# PP5_MIDI.net
KiCad netlist of a schematic drawn in Altium Designer
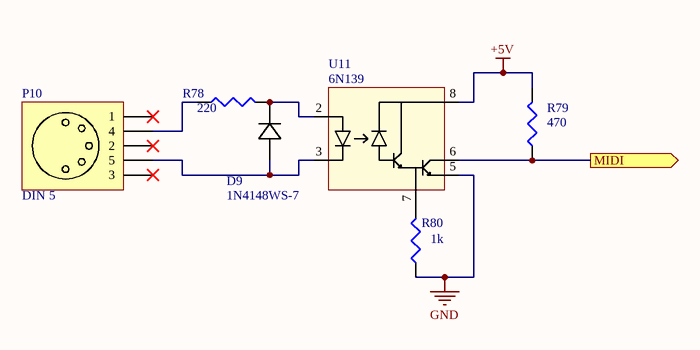
[diagram p0: PP5_MIDI.SchDoc]

(export (version "E")
  (design (tool "Eeschema 10.0.6"))
  (components
    (comp (ref "D9")
      (value "1N4148WS-7")
      (footprint "SOD323-M")
      (description "Diode signaux faibles")
      (libsource (lib "Michel") (part "1N4148WS-7"))
    )
    (comp (ref "P10")
      (value "DIN 5")
      (footprint "PRO SIGNAL_PSG03463")
      (description "DIN 5pin")
      (libsource (lib "Michel") (part "DIN 5pin"))
    )
    (comp (ref "R78")
      (value "220")
      (footprint "RESC1608X05")
      (description "Capacitor")
      (fields (field (name "Comment") "Cap 220"))
      (libsource (lib "Michel") (part "Res3"))
    )
    (comp (ref "R79")
      (value "470")
      (footprint "RESC1608X05")
      (description "Resistor")
      (fields (field (name "Comment") "Res 470"))
      (libsource (lib "Michel") (part "Res3"))
    )
    (comp (ref "R80")
      (value "1k")
      (footprint "RESC1608X05")
      (description "Resistor")
      (fields (field (name "Comment") "Res 1k"))
      (libsource (lib "Michel") (part "Res3"))
    )
    (comp (ref "U11")
      (value "6N139")
      (footprint "SOIC127P970X356-8N")
      (description "Optocoupler")
      (libsource (lib "Michel") (part "6N139"))
    )
  )
  (nets
    (net (code "1") (name "+5V") (class "Default")
      (node (ref "R79") (pin "2") (pinfunction "2_2") (pintype "passive"))
      (node (ref "U11") (pin "8") (pinfunction "B1_8") (pintype "passive"))
    )
    (net (code "2") (name "/MIDI") (class "Default")
      (node (ref "R79") (pin "1") (pinfunction "1_1") (pintype "passive"))
      (node (ref "U11") (pin "6") (pinfunction "B1_6") (pintype "passive"))
    )
    (net (code "3") (name "GND") (class "Default")
      (node (ref "R80") (pin "1") (pinfunction "1_1") (pintype "passive"))
      (node (ref "U11") (pin "5") (pinfunction "B1_5") (pintype "passive"))
    )
    (net (code "4") (name "Net-(D9-Pad2)") (class "Default")
      (node (ref "D9") (pin "2") (pinfunction "2_2") (pintype "passive"))
      (node (ref "P10") (pin "5") (pinfunction "5_5") (pintype "passive"))
      (node (ref "U11") (pin "3") (pinfunction "B1_3") (pintype "passive"))
    )
    (net (code "5") (name "Net-(P10-Pad4)") (class "Default")
      (node (ref "P10") (pin "4") (pinfunction "4_4") (pintype "passive"))
      (node (ref "R78") (pin "1") (pinfunction "1_1") (pintype "passive"))
    )
    (net (code "6") (name "Net-(R80-Pad2)") (class "Default")
      (node (ref "R80") (pin "2") (pinfunction "2_2") (pintype "passive"))
      (node (ref "U11") (pin "7") (pinfunction "B1_7") (pintype "passive"))
    )
    (net (code "7") (name "Net-(U11-B2)") (class "Default")
      (node (ref "D9") (pin "1") (pinfunction "1_1") (pintype "passive"))
      (node (ref "R78") (pin "2") (pinfunction "2_2") (pintype "passive"))
      (node (ref "U11") (pin "2") (pinfunction "B2_2") (pintype "passive"))
    )
    (net (code "8") (name "unconnected-(P10-Pad1)") (class "Default")
      (node (ref "P10") (pin "1") (pinfunction "1_1") (pintype "passive+no_connect"))
    )
    (net (code "9") (name "unconnected-(P10-Pad2)") (class "Default")
      (node (ref "P10") (pin "2") (pinfunction "2_2") (pintype "passive+no_connect"))
    )
    (net (code "10") (name "unconnected-(P10-Pad3)") (class "Default")
      (node (ref "P10") (pin "3") (pinfunction "3_3") (pintype "passive+no_connect"))
    )
  )
)
